# MAIN.net
KiCad netlist of a schematic drawn in Altium Designer
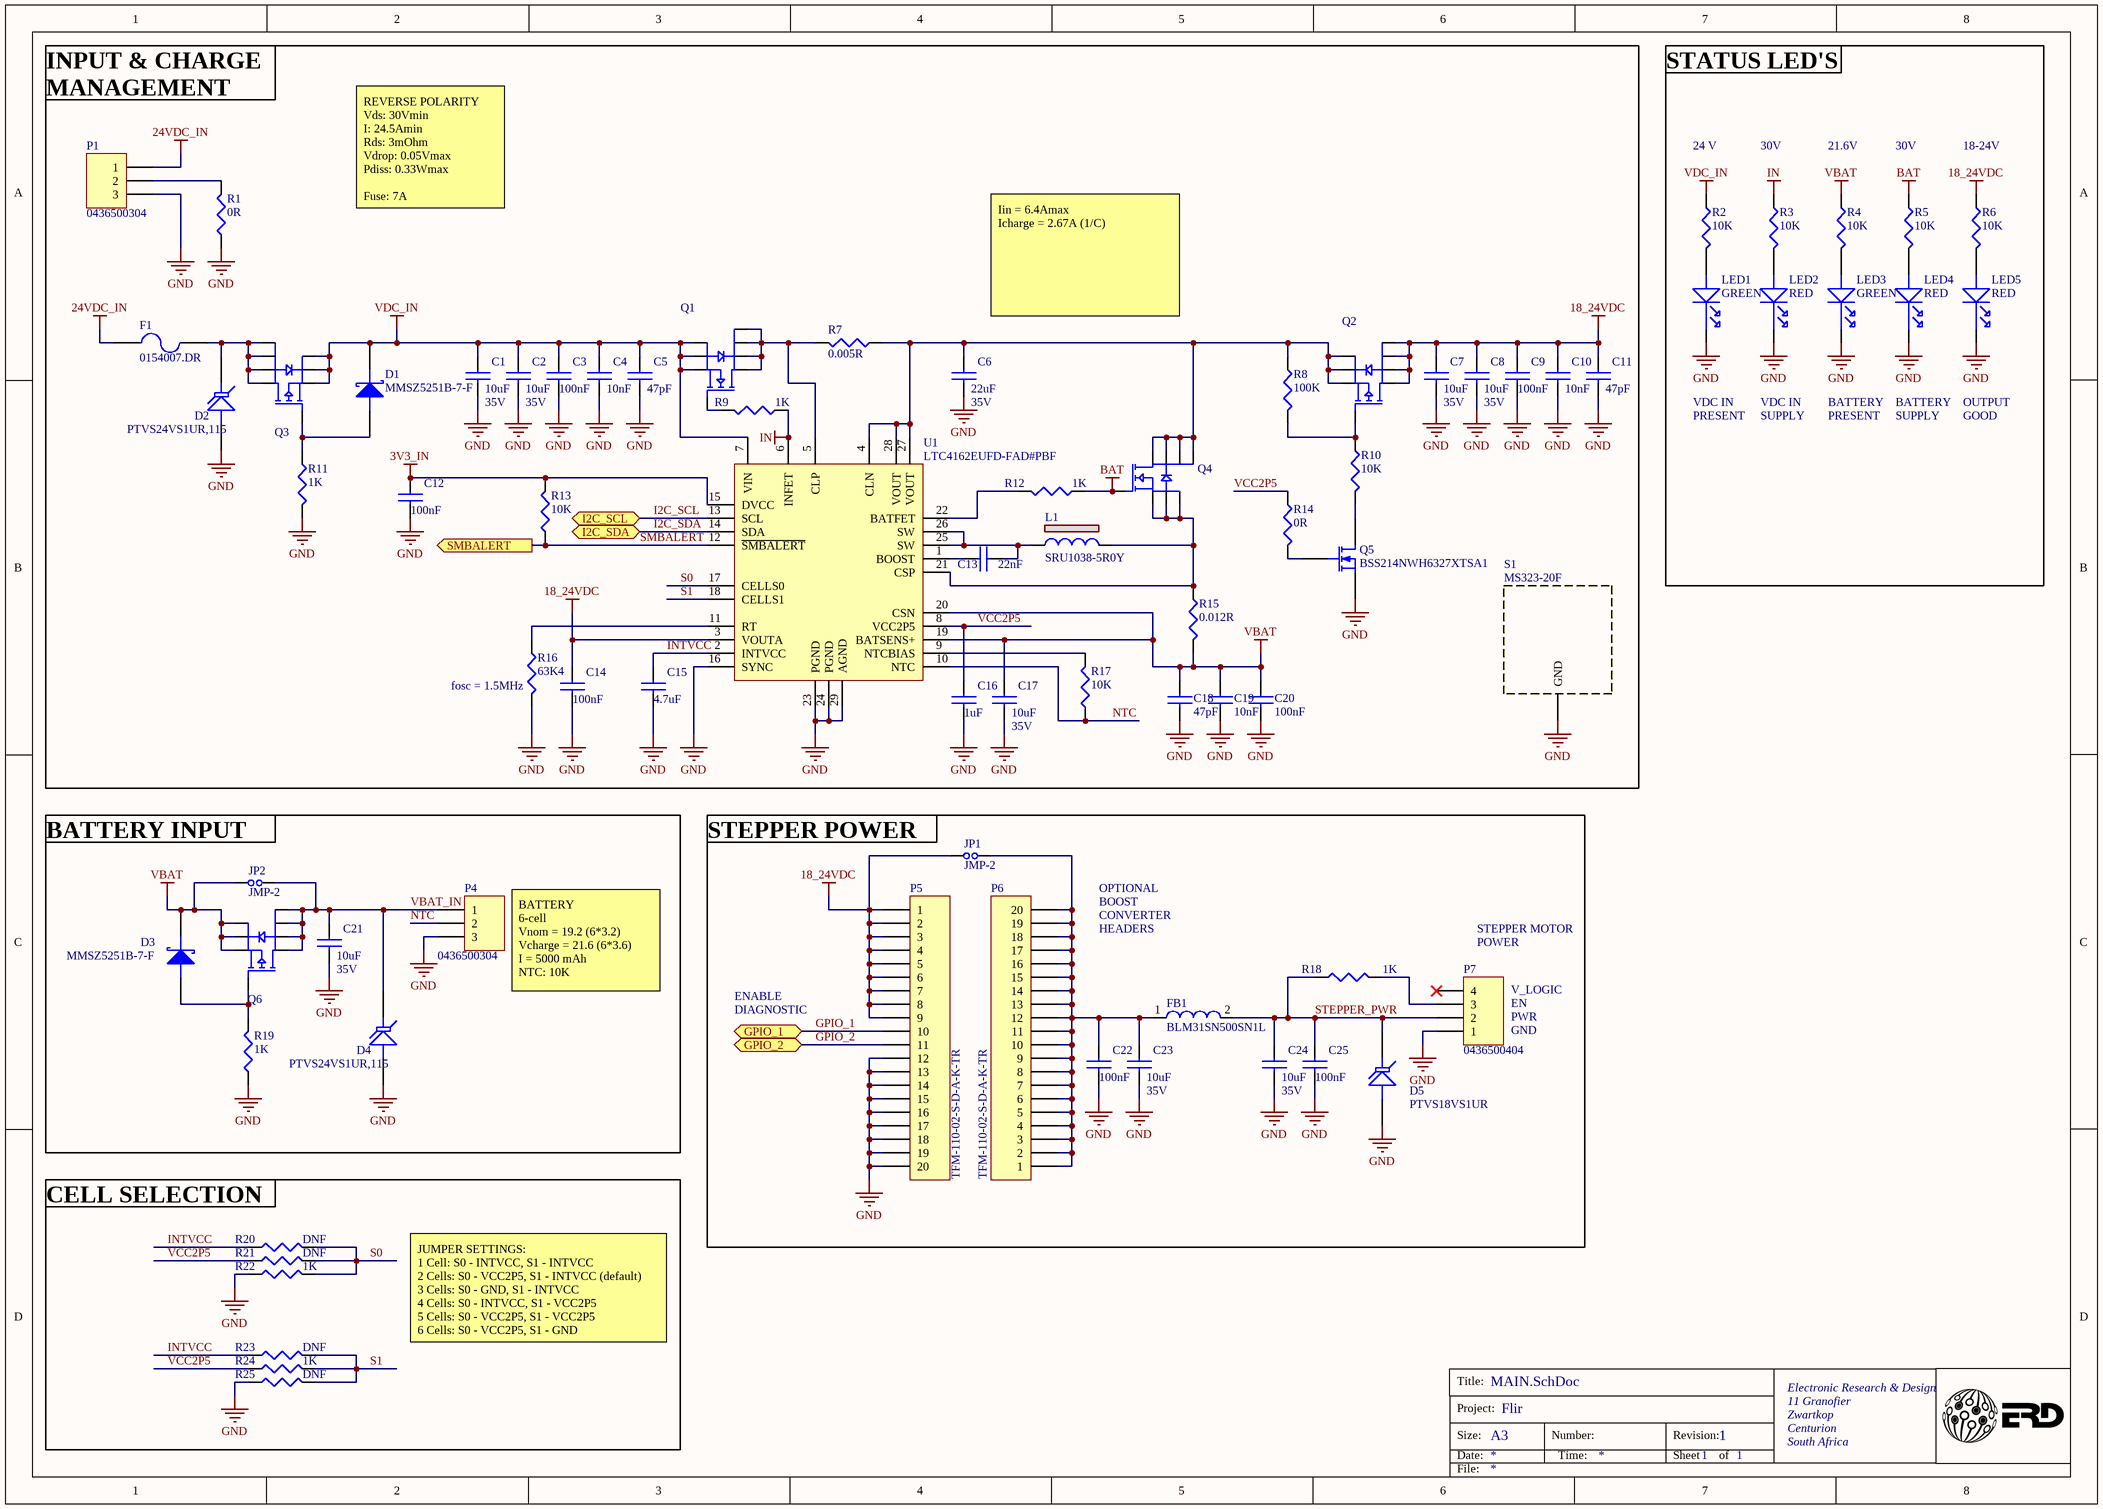
[diagram p0: MAIN.SchDoc]

(export (version "E")
  (design (tool "Eeschema 10.0.6"))
  (components
    (comp (ref "C1")
      (value "10uF")
      (footprint "CC0805")
      (description "CAP CER 10UF 35V 10% X5R 0805")
      (fields
        (field (name "MANUFACTURER") "Murata")
        (field (name "PART NUMBER") "GRM21BR6YA106KE43L")
        (field (name "VOLTAGE RATING") "35V")
      )
      (libsource (lib "ERD TiAm") (part "CAP CER 0.1UF 10V 10% X5R 0402"))
    )
    (comp (ref "C2")
      (value "10uF")
      (footprint "CC0805")
      (description "CAP CER 10UF 35V 10% X5R 0805")
      (fields
        (field (name "MANUFACTURER") "Murata")
        (field (name "PART NUMBER") "GRM21BR6YA106KE43L")
        (field (name "VOLTAGE RATING") "35V")
      )
      (libsource (lib "ERD TiAm") (part "CAP CER 0.1UF 10V 10% X5R 0402"))
    )
    (comp (ref "C3")
      (value "100nF")
      (footprint "CC0402")
      (description "CAP CER 0.1UF 50V 10% X7R 0402")
      (fields (field (name "MANUFACTURER") "Murata") (field (name "PART NUMBER") "GCM155R71H104KE02D"))
      (libsource (lib "ERD TiAm") (part "CAP CER 0.1UF 10V 10% X5R 0402"))
    )
    (comp (ref "C4")
      (value "10nF")
      (footprint "CC0402")
      (description "CAP CER 10NF 50V 10% X7R 0402")
      (fields (field (name "MANUFACTURER") "Murata") (field (name "PART NUMBER") "GRM155R71H103KA88J"))
      (libsource (lib "ERD TiAm") (part "CAP CER 0.1UF 10V 10% X5R 0402"))
    )
    (comp (ref "C5")
      (value "47pF")
      (footprint "CC0402")
      (description "CAP CER 47PF 50V 5% C0G/NP0 0402")
      (fields (field (name "MANUFACTURER") "Murata") (field (name "PART NUMBER") "GCM1555C1H470JA16D"))
      (libsource (lib "ERD TiAm") (part "CAP CER 0.1UF 10V 10% X5R 0402"))
    )
    (comp (ref "C6")
      (value "22uF")
      (footprint "RC1206")
      (description "CAP CER 22UF 35V 20% X5R 1206")
      (fields
        (field (name "MANUFACTURER") "Murata")
        (field (name "PART NUMBER") "C3216X5R1V226M160AC")
        (field (name "VOLTAGE RATING") "35V")
      )
      (libsource (lib "ERD TiAm") (part "CAP CER 0.1UF 10V 10% X5R 0402"))
    )
    (comp (ref "C7")
      (value "10uF")
      (footprint "CC0805")
      (description "CAP CER 10UF 35V 10% X5R 0805")
      (fields
        (field (name "MANUFACTURER") "Murata")
        (field (name "PART NUMBER") "GRM21BR6YA106KE43L")
        (field (name "VOLTAGE RATING") "35V")
      )
      (libsource (lib "ERD TiAm") (part "CAP CER 0.1UF 10V 10% X5R 0402"))
    )
    (comp (ref "C8")
      (value "10uF")
      (footprint "CC0805")
      (description "CAP CER 10UF 35V 10% X5R 0805")
      (fields
        (field (name "MANUFACTURER") "Murata")
        (field (name "PART NUMBER") "GRM21BR6YA106KE43L")
        (field (name "VOLTAGE RATING") "35V")
      )
      (libsource (lib "ERD TiAm") (part "CAP CER 0.1UF 10V 10% X5R 0402"))
    )
    (comp (ref "C9")
      (value "100nF")
      (footprint "CC0402")
      (description "CAP CER 0.1UF 50V 10% X7R 0402")
      (fields (field (name "MANUFACTURER") "Murata") (field (name "PART NUMBER") "GCM155R71H104KE02D"))
      (libsource (lib "ERD TiAm") (part "CAP CER 0.1UF 10V 10% X5R 0402"))
    )
    (comp (ref "C10")
      (value "10nF")
      (footprint "CC0402")
      (description "CAP CER 10NF 50V 10% X7R 0402")
      (fields (field (name "MANUFACTURER") "Murata") (field (name "PART NUMBER") "GRM155R71H103KA88J"))
      (libsource (lib "ERD TiAm") (part "CAP CER 0.1UF 10V 10% X5R 0402"))
    )
    (comp (ref "C11")
      (value "47pF")
      (footprint "CC0402")
      (description "CAP CER 47PF 50V 5% C0G/NP0 0402")
      (fields (field (name "MANUFACTURER") "Murata") (field (name "PART NUMBER") "GCM1555C1H470JA16D"))
      (libsource (lib "ERD TiAm") (part "CAP CER 0.1UF 10V 10% X5R 0402"))
    )
    (comp (ref "C12")
      (value "100nF")
      (footprint "CC0402")
      (description "CAP CER 0.1UF 50V 10% X7R 0402")
      (fields (field (name "MANUFACTURER") "Murata") (field (name "PART NUMBER") "GCM155R71H104KE02D"))
      (libsource (lib "ERD TiAm") (part "CAP CER 0.1UF 10V 10% X5R 0402"))
    )
    (comp (ref "C13")
      (value "22nF")
      (footprint "CC0402")
      (description "CAP CER 0.022UF 50V 10% X7R 0402")
      (fields (field (name "MANUFACTURER") "Murata") (field (name "PART NUMBER") "GCM155R71H223KA55D"))
      (libsource (lib "ERD TiAm") (part "CAP CER 0.1UF 10V 10% X5R 0402"))
    )
    (comp (ref "C14")
      (value "100nF")
      (footprint "CC0402")
      (description "CAP CER 0.1UF 50V 10% X7R 0402")
      (fields (field (name "MANUFACTURER") "Murata") (field (name "PART NUMBER") "GCM155R71H104KE02D"))
      (libsource (lib "ERD TiAm") (part "CAP CER 0.1UF 10V 10% X5R 0402"))
    )
    (comp (ref "C15")
      (value "4.7uF")
      (footprint "CC0603")
      (description "CAP CER 4.7UF 25V 10% X5R 0603")
      (fields (field (name "MANUFACTURER") "Murata") (field (name "PART NUMBER") "GRM188R61E475KE11D"))
      (libsource (lib "ERD TiAm") (part "CAP CER 0.1UF 10V 10% X5R 0402"))
    )
    (comp (ref "C16")
      (value "1uF")
      (footprint "CC0402")
      (description "CAP CER 1UF 10V 20% X5R 0402")
      (fields (field (name "MANUFACTURER") "Murata") (field (name "PART NUMBER") "GRM153R61A105ME95D"))
      (libsource (lib "ERD TiAm") (part "CAP CER 0.1UF 10V 10% X5R 0402"))
    )
    (comp (ref "C17")
      (value "10uF")
      (footprint "CC0805")
      (description "CAP CER 10UF 35V 10% X5R 0805")
      (fields
        (field (name "MANUFACTURER") "Murata")
        (field (name "PART NUMBER") "GRM21BR6YA106KE43L")
        (field (name "VOLTAGE RATING") "35V")
      )
      (libsource (lib "ERD TiAm") (part "CAP CER 0.1UF 10V 10% X5R 0402"))
    )
    (comp (ref "C18")
      (value "47pF")
      (footprint "CC0402")
      (description "CAP CER 47PF 50V 5% C0G/NP0 0402")
      (fields (field (name "MANUFACTURER") "Murata") (field (name "PART NUMBER") "GCM1555C1H470JA16D"))
      (libsource (lib "ERD TiAm") (part "CAP CER 0.1UF 10V 10% X5R 0402"))
    )
    (comp (ref "C19")
      (value "10nF")
      (footprint "CC0402")
      (description "CAP CER 10NF 50V 10% X7R 0402")
      (fields (field (name "MANUFACTURER") "Murata") (field (name "PART NUMBER") "GRM155R71H103KA88J"))
      (libsource (lib "ERD TiAm") (part "CAP CER 0.1UF 10V 10% X5R 0402"))
    )
    (comp (ref "C20")
      (value "100nF")
      (footprint "CC0402")
      (description "CAP CER 0.1UF 50V 10% X7R 0402")
      (fields (field (name "MANUFACTURER") "Murata") (field (name "PART NUMBER") "GCM155R71H104KE02D"))
      (libsource (lib "ERD TiAm") (part "CAP CER 0.1UF 10V 10% X5R 0402"))
    )
    (comp (ref "C21")
      (value "10uF")
      (footprint "CC0805")
      (description "CAP CER 10UF 35V 10% X5R 0805")
      (fields
        (field (name "MANUFACTURER") "Murata")
        (field (name "PART NUMBER") "GRM21BR6YA106KE43L")
        (field (name "VOLTAGE RATING") "35V")
      )
      (libsource (lib "ERD TiAm") (part "CAP CER 0.1UF 10V 10% X5R 0402"))
    )
    (comp (ref "C22")
      (value "100nF")
      (footprint "CC0402")
      (description "CAP CER 0.1UF 50V 10% X7R 0402")
      (fields (field (name "MANUFACTURER") "Murata") (field (name "PART NUMBER") "GCM155R71H104KE02D"))
      (libsource (lib "ERD TiAm") (part "CAP CER 0.1UF 10V 10% X5R 0402"))
    )
    (comp (ref "C23")
      (value "10uF")
      (footprint "CC0805")
      (description "CAP CER 10UF 35V 10% X5R 0805")
      (fields
        (field (name "MANUFACTURER") "Murata")
        (field (name "PART NUMBER") "GRM21BR6YA106KE43L")
        (field (name "VOLTAGE RATING") "35V")
      )
      (libsource (lib "ERD TiAm") (part "CAP CER 0.1UF 10V 10% X5R 0402"))
    )
    (comp (ref "C24")
      (value "10uF")
      (footprint "CC0805")
      (description "CAP CER 10UF 35V 10% X5R 0805")
      (fields
        (field (name "MANUFACTURER") "Murata")
        (field (name "PART NUMBER") "GRM21BR6YA106KE43L")
        (field (name "VOLTAGE RATING") "35V")
      )
      (libsource (lib "ERD TiAm") (part "CAP CER 0.1UF 10V 10% X5R 0402"))
    )
    (comp (ref "C25")
      (value "100nF")
      (footprint "CC0402")
      (description "CAP CER 0.1UF 50V 10% X7R 0402")
      (fields (field (name "MANUFACTURER") "Murata") (field (name "PART NUMBER") "GCM155R71H104KE02D"))
      (libsource (lib "ERD TiAm") (part "CAP CER 0.1UF 10V 10% X5R 0402"))
    )
    (comp (ref "D1")
      (value "MMSZ5251B-7-F")
      (footprint "SOD123W")
      (description "DIODE, ZENER, 22V, 5%, 500mW, SOD123")
      (libsource (lib "GadgetJD") (part "DIODE SCHOTTKY"))
    )
    (comp (ref "D2")
      (value "PTVS24VS1UR,115")
      (footprint "SOD123W")
      (description "DIODE, TVS, 24V, 400W, SOD123W")
      (libsource (lib "Miscellaneous Devices") (part "Tranzorb"))
    )
    (comp (ref "D3")
      (value "MMSZ5251B-7-F")
      (footprint "SOD123W")
      (description "DIODE, ZENER, 22V, 5%, 500mW, SOD123")
      (libsource (lib "GadgetJD") (part "DIODE SCHOTTKY"))
    )
    (comp (ref "D4")
      (value "PTVS24VS1UR,115")
      (footprint "SOD123W")
      (description "DIODE, TVS, 24V, 400W, SOD123W")
      (libsource (lib "Miscellaneous Devices") (part "Tranzorb"))
    )
    (comp (ref "D5")
      (value "PTVS18VS1UR")
      (footprint "SOD123W")
      (description "DIODE, TVS, 24V, 400W, SOD123W")
      (fields (field (name "PARTNUMBER") "PTVS24VS1UR,115"))
      (libsource (lib "Miscellaneous Devices") (part "Tranzorb"))
    )
    (comp (ref "F1")
      (value "0154007.DR")
      (footprint "OMNI_BLOK")
      (description "FUSE, OMNIBLOK, 125VAC/DC, 7A, Fast, SMD")
      (fields (field (name "MANUFACTURER") "Littlefuse"))
      (libsource (lib "Miscellaneous Devices") (part "Fuse 2"))
    )
    (comp (ref "FB1")
      (value "BLM31SN500SN1L")
      (footprint "RC1206")
      (description "FERRITE, 12A, 1.6mOhm, 1206")
      (libsource (lib "BEAGLEBONEBLACK_REV A5B") (part "FER_180_200_0"))
    )
    (comp (ref "JP1")
      (value "JMP-2")
      (description "Solder Jumper 2 pin")
      (libsource (lib "ERD TiAm") (part "JMP-2"))
    )
    (comp (ref "JP2")
      (value "JMP-2")
      (description "Solder Jumper 2 pin")
      (libsource (lib "ERD TiAm") (part "JMP-2"))
    )
    (comp (ref "L1")
      (value "SRU1038-5R0Y")
      (footprint "MSS1260")
      (description "IND, Power, Shielded, 5uH, 4.8A Isat, 14.5 mOHM, SMD")
      (fields (field (name "MANUFACTURER") "Bourns"))
      (libsource (lib "SCH") (part "MSS1260X"))
    )
    (comp (ref "LED1")
      (value "GREEN")
      (footprint "LED0603")
      (description "LED, GRN, 65 mcd, 0603")
      (fields (field (name "PARTNUMBER") "LTST-C194KGKT"))
      (libsource (lib "*") (part "LED"))
    )
    (comp (ref "LED2")
      (value "RED")
      (footprint "LED0603")
      (description "LED, GRN, 65 mcd, 0603")
      (fields (field (name "PARTNUMBER") "LTST-C194KRKT"))
      (libsource (lib "*") (part "LED"))
    )
    (comp (ref "LED3")
      (value "GREEN")
      (footprint "LED0603")
      (description "LED, GRN, 65 mcd, 0603")
      (fields (field (name "PARTNUMBER") "LTST-C194KGKT"))
      (libsource (lib "*") (part "LED"))
    )
    (comp (ref "LED4")
      (value "RED")
      (footprint "LED0603")
      (description "LED, GRN, 65 mcd, 0603")
      (fields (field (name "PARTNUMBER") "LTST-C194KRKT"))
      (libsource (lib "*") (part "LED"))
    )
    (comp (ref "LED5")
      (value "RED")
      (footprint "LED0603")
      (description "LED, GRN, 65 mcd, 0603")
      (fields (field (name "PARTNUMBER") "LTST-C194KRKT"))
      (libsource (lib "*") (part "LED"))
    )
    (comp (ref "P1")
      (value "0436500304")
      (footprint "HDR1X3")
      (description "Header, MicroFit, RA, 3-circuit, 3mm pitch, TH")
      (fields (field (name "MANUFACTURER") "Molex") (field (name "MATING PART") "0436450300"))
      (libsource (lib "") (part "Header 3_1"))
    )
    (comp (ref "P4")
      (value "0436500304")
      (footprint "HDR1X3")
      (description "Header, MicroFit, RA, 3-circuit, 3mm pitch, TH")
      (fields (field (name "MANUFACTURER") "Molex") (field (name "MATING PART") "0436450300"))
      (libsource (lib "Miscellaneous Connectors") (part "Header 3"))
    )
    (comp (ref "P5")
      (value "TFM-110-02-S-D-A-K-TR")
      (footprint "HDR1X20")
      (description "Header, 20 POS, 1.27mm PITCH, SMD")
      (libsource (lib "") (part "Header 20_1"))
    )
    (comp (ref "P6")
      (value "TFM-110-02-S-D-A-K-TR")
      (footprint "HDR1X20")
      (description "Header, 20 POS, 1.27mm PITCH, SMD")
      (libsource (lib "Miscellaneous Connectors") (part "Header 20"))
    )
    (comp (ref "P7")
      (value "0436500404")
      (footprint "HDR1X4")
      (description "Header, MicroFit, RA, 4-circuit, 3mm pitch, TH")
      (fields (field (name "MANUFACTURER") "Molex") (field (name "MATING PART") "0436450400"))
      (libsource (lib "Miscellaneous Connectors") (part "Header 4"))
    )
    (comp (ref "Q1")
      (value "BSC054N04NSGATMA1")
      (footprint "PG-TDSON-8 - alternate")
      (description "N-channel FET, 40V, 17A, 5.4mOhm, TDSON-8")
      (libsource (lib "SCH") (part "BSC190N15NS3"))
    )
    (comp (ref "Q2")
      (value "BSC030P03NS3GAUMA1")
      (footprint "PG-TDSON-8 - alternate")
      (description "P-channel FET, 30V, 100A, 3mOhm, TDSON-8")
      (libsource (lib "ERD TiAm") (part "p_Channel"))
    )
    (comp (ref "Q3")
      (value "BSC030P03NS3GAUMA1")
      (footprint "PG-TDSON-8 - alternate")
      (description "P-channel FET, 30V, 100A, 3mOhm, TDSON-8")
      (libsource (lib "ERD TiAm") (part "p_Channel"))
    )
    (comp (ref "Q4")
      (value "BSC054N04NSGATMA1")
      (footprint "PG-TDSON-8 - alternate")
      (description "N-channel FET, 40V, 17A, 5.4mOhm, TDSON-8")
      (libsource (lib "SCH") (part "BSC190N15NS3"))
    )
    (comp (ref "Q5")
      (value "BSS214NWH6327XTSA1")
      (footprint "ERD TiAm:SOT323")
      (description "N-Channel FET, 20V, 1.5A, 140mOhm, SOT323")
      (fields (field (name "PUBLISHER") "Altium Limited"))
      (libsource (lib "Miscellaneous Devices") (part "MOSFET-N"))
    )
    (comp (ref "Q6")
      (value "BSC030P03NS3GAUMA1")
      (footprint "PG-TDSON-8 - alternate")
      (description "P-channel FET, 30V, 100A, 3mOhm, TDSON-8")
      (libsource (lib "ERD TiAm") (part "p_Channel"))
    )
    (comp (ref "R1")
      (value "0R")
      (footprint "RC0402")
      (description "RES, 0 OHM, 1/16W, 1%, 0402")
      (fields (field (name "MANUFACTURER") "Yageo") (field (name "PARTNUMBER") "RC0402FR-070RL"))
      (libsource (lib "ERD TiAm") (part "RES_10K_1/16W_1%_0402"))
    )
    (comp (ref "R2")
      (value "10K")
      (footprint "RC0402")
      (description "RES, 10K OHM, 1/16W, 1%, 0402")
      (fields (field (name "MANUFACTURER") "Yageo") (field (name "PART NUMBER") "RC0402FR-0710KL"))
      (libsource (lib "ERD TiAm") (part "RES_10K_1/16W_1%_0402"))
    )
    (comp (ref "R3")
      (value "10K")
      (footprint "RC0402")
      (description "RES, 10K OHM, 1/16W, 1%, 0402")
      (fields (field (name "MANUFACTURER") "Yageo") (field (name "PART NUMBER") "RC0402FR-0710KL"))
      (libsource (lib "ERD TiAm") (part "RES_10K_1/16W_1%_0402"))
    )
    (comp (ref "R4")
      (value "10K")
      (footprint "RC0402")
      (description "RES, 10K OHM, 1/16W, 1%, 0402")
      (fields (field (name "MANUFACTURER") "Yageo") (field (name "PART NUMBER") "RC0402FR-0710KL"))
      (libsource (lib "ERD TiAm") (part "RES_10K_1/16W_1%_0402"))
    )
    (comp (ref "R5")
      (value "10K")
      (footprint "RC0402")
      (description "RES, 10K OHM, 1/16W, 1%, 0402")
      (fields (field (name "MANUFACTURER") "Yageo") (field (name "PART NUMBER") "RC0402FR-0710KL"))
      (libsource (lib "ERD TiAm") (part "RES_10K_1/16W_1%_0402"))
    )
    (comp (ref "R6")
      (value "10K")
      (footprint "RC0402")
      (description "RES, 10K OHM, 1/16W, 1%, 0402")
      (fields (field (name "MANUFACTURER") "Yageo") (field (name "PART NUMBER") "RC0402FR-0710KL"))
      (libsource (lib "ERD TiAm") (part "RES_10K_1/16W_1%_0402"))
    )
    (comp (ref "R7")
      (value "0.005R")
      (footprint "RC1206W")
      (description "RES, 0.005 OHM, 1W, 1%, 1206W")
      (fields
        (field (name "MANUFACTURER") "Susumu")
        (field (name "MANUFACTURER PART NUMBER") "KRL3216T4A-M-R005-F-T1")
      )
      (libsource (lib "ERD TiAm") (part "RES_0_1/16W_1%_0402"))
    )
    (comp (ref "R8")
      (value "100K")
      (footprint "RC0402")
      (description "RES, 100K OHM, 1/16W, 1%, 0402")
      (fields (field (name "MANUFACTURER") "Yageo") (field (name "PART NUMBER") "RC0402FR-07100KL"))
      (libsource (lib "ERD TiAm") (part "RES_10K_1/16W_1%_0402"))
    )
    (comp (ref "R9")
      (value "1K")
      (footprint "RC0402")
      (description "RES, 1K OHM, 1/16W, 1%, 0402")
      (fields (field (name "MANUFACTURER") "Yageo") (field (name "PARTNUMBER") "RC0402FR-071KL"))
      (libsource (lib "ERD TiAm") (part "RES_10K_1/16W_1%_0402"))
    )
    (comp (ref "R10")
      (value "10K")
      (footprint "RC0402")
      (description "RES, 10K OHM, 1/16W, 1%, 0402")
      (fields (field (name "MANUFACTURER") "Yageo") (field (name "PART NUMBER") "RC0402FR-0710KL"))
      (libsource (lib "ERD TiAm") (part "RES_10K_1/16W_1%_0402"))
    )
    (comp (ref "R11")
      (value "1K")
      (footprint "RC0402")
      (description "RES, 1K OHM, 1/16W, 1%, 0402")
      (fields (field (name "MANUFACTURER") "Yageo") (field (name "PARTNUMBER") "RC0402FR-071KL"))
      (libsource (lib "ERD TiAm") (part "RES_10K_1/16W_1%_0402"))
    )
    (comp (ref "R12")
      (value "1K")
      (footprint "RC0402")
      (description "RES, 1K OHM, 1/16W, 1%, 0402")
      (fields (field (name "MANUFACTURER") "Yageo") (field (name "PARTNUMBER") "RC0402FR-071KL"))
      (libsource (lib "ERD TiAm") (part "RES_10K_1/16W_1%_0402"))
    )
    (comp (ref "R13")
      (value "10K")
      (footprint "RC0402")
      (description "RES, 10K OHM, 1/16W, 1%, 0402")
      (fields (field (name "MANUFACTURER") "Yageo") (field (name "PART NUMBER") "RC0402FR-0710KL"))
      (libsource (lib "ERD TiAm") (part "RES_10K_1/16W_1%_0402"))
    )
    (comp (ref "R14")
      (value "0R")
      (footprint "RC0402")
      (description "RES, 0 OHM, 1/16W, 1%, 0402")
      (fields (field (name "MANUFACTURER") "Yageo") (field (name "PARTNUMBER") "RC0402FR-070RL"))
      (libsource (lib "ERD TiAm") (part "RES_10K_1/16W_1%_0402"))
    )
    (comp (ref "R15")
      (value "0.012R")
      (footprint "RC1206")
      (description "RES, 0.012 OHM, 1W, 1%, 1206")
      (fields
        (field (name "MANUFACTURER") "Panasonic")
        (field (name "MANUFACTURER PART NUMBER") "ERJ-8CWFR010V")
      )
      (libsource (lib "ERD TiAm") (part "RES_0_1/16W_1%_0402"))
    )
    (comp (ref "R16")
      (value "63K4")
      (footprint "RC0402")
      (description "RES, 63K4 OHM, 1/16W, 1%, 0402")
      (fields (field (name "MANUFACTURER") "Yageo") (field (name "PART NUMBER") "RC0402FR-0763K4L"))
      (libsource (lib "ERD TiAm") (part "RES_10K_1/16W_1%_0402"))
    )
    (comp (ref "R17")
      (value "10K")
      (footprint "RC0402")
      (description "RES, 10K OHM, 1/16W, 1%, 0402")
      (fields (field (name "MANUFACTURER") "Yageo") (field (name "PART NUMBER") "RC0402FR-0710KL"))
      (libsource (lib "ERD TiAm") (part "RES_10K_1/16W_1%_0402"))
    )
    (comp (ref "R18")
      (value "1K")
      (footprint "RC0402")
      (description "RES, 1K OHM, 1/16W, 1%, 0402")
      (fields (field (name "MANUFACTURER") "Yageo") (field (name "PARTNUMBER") "RC0402FR-071KL"))
      (libsource (lib "ERD TiAm") (part "RES_10K_1/16W_1%_0402"))
    )
    (comp (ref "R19")
      (value "1K")
      (footprint "RC0402")
      (description "RES, 1K OHM, 1/16W, 1%, 0402")
      (fields (field (name "MANUFACTURER") "Yageo") (field (name "PARTNUMBER") "RC0402FR-071KL"))
      (libsource (lib "ERD TiAm") (part "RES_10K_1/16W_1%_0402"))
    )
    (comp (ref "R20")
      (value "DNF")
      (footprint "RC0402")
      (description "RES, 1K OHM, 1/16W, 1%, 0402")
      (fields (field (name "MANUFACTURER") "Yageo") (field (name "PART NUMBER") "RC0402FR-071KL"))
      (libsource (lib "ERD TiAm") (part "RES_10K_1/16W_1%_0402"))
    )
    (comp (ref "R21")
      (value "DNF")
      (footprint "RC0402")
      (description "RES, 1K OHM, 1/16W, 1%, 0402")
      (fields (field (name "MANUFACTURER") "Yageo") (field (name "PART NUMBER") "RC0402FR-071KL"))
      (libsource (lib "ERD TiAm") (part "RES_10K_1/16W_1%_0402"))
    )
    (comp (ref "R22")
      (value "1K")
      (footprint "RC0402")
      (description "RES, 1K OHM, 1/16W, 1%, 0402")
      (fields (field (name "MANUFACTURER") "Yageo") (field (name "PART NUMBER") "RC0402FR-071KL"))
      (libsource (lib "ERD TiAm") (part "RES_10K_1/16W_1%_0402"))
    )
    (comp (ref "R23")
      (value "DNF")
      (footprint "RC0402")
      (description "RES, 1K OHM, 1/16W, 1%, 0402")
      (fields (field (name "MANUFACTURER") "Yageo") (field (name "PART NUMBER") "RC0402FR-071KL"))
      (libsource (lib "ERD TiAm") (part "RES_10K_1/16W_1%_0402"))
    )
    (comp (ref "R24")
      (value "1K")
      (footprint "RC0402")
      (description "RES, 1K OHM, 1/16W, 1%, 0402")
      (fields (field (name "MANUFACTURER") "Yageo") (field (name "PART NUMBER") "RC0402FR-071KL"))
      (libsource (lib "ERD TiAm") (part "RES_10K_1/16W_1%_0402"))
    )
    (comp (ref "R25")
      (value "DNF")
      (footprint "RC0402")
      (description "RES, 1K OHM, 1/16W, 1%, 0402")
      (fields (field (name "MANUFACTURER") "Yageo") (field (name "PART NUMBER") "RC0402FR-071KL"))
      (libsource (lib "ERD TiAm") (part "RES_10K_1/16W_1%_0402"))
    )
    (comp (ref "S1")
      (value "MS323-20F")
      (footprint "2118727-2")
      (description "RF Shield, 32.9mm x 24.4mm x 4.7mm")
      (fields (field (name "MATING PART") "MS323-20C"))
      (libsource (lib "ERD TiAm") (part "BMI-S-206-F"))
    )
    (comp (ref "U1")
      (value "LTC4162EUFD-FAD#PBF")
      (footprint "QFN-28 LTC")
      (description "Multi-Cell LiFePO4 Charger, 35V, 3.2A, QFN-28")
      (libsource (lib "ERD TiAm") (part "LTC4162"))
    )
  )
  (nets
    (net (code "1") (name "/GPIO_1") (class "Default")
      (node (ref "P5") (pin "10") (pinfunction "10_10") (pintype "passive"))
    )
    (net (code "2") (name "/GPIO_2") (class "Default")
      (node (ref "P5") (pin "11") (pinfunction "11_11") (pintype "passive"))
    )
    (net (code "3") (name "/I2C_SCL") (class "Default")
      (node (ref "U1") (pin "13") (pinfunction "SCL_13") (pintype "passive"))
    )
    (net (code "4") (name "/I2C_SDA") (class "Default")
      (node (ref "U1") (pin "14") (pinfunction "SDA_14") (pintype "passive"))
    )
    (net (code "5") (name "/INTVCC") (class "Default")
      (node (ref "C15") (pin "1") (pinfunction "1_1") (pintype "passive"))
      (node (ref "R20") (pin "1") (pinfunction "1_1") (pintype "passive"))
      (node (ref "R23") (pin "1") (pinfunction "1_1") (pintype "passive"))
      (node (ref "U1") (pin "2") (pinfunction "INTVCC_2") (pintype "passive"))
    )
    (net (code "6") (name "/NTC") (class "Default")
      (node (ref "P4") (pin "2") (pinfunction "2_2") (pintype "passive"))
      (node (ref "R17") (pin "1") (pinfunction "1_1") (pintype "passive"))
      (node (ref "U1") (pin "10") (pinfunction "NTC_10") (pintype "passive"))
    )
    (net (code "7") (name "/S0") (class "Default")
      (node (ref "R20") (pin "2") (pinfunction "2_2") (pintype "passive"))
      (node (ref "R21") (pin "2") (pinfunction "2_2") (pintype "passive"))
      (node (ref "R22") (pin "2") (pinfunction "2_2") (pintype "passive"))
      (node (ref "U1") (pin "17") (pinfunction "CELLS0_17") (pintype "passive"))
    )
    (net (code "8") (name "/S1") (class "Default")
      (node (ref "R23") (pin "2") (pinfunction "2_2") (pintype "passive"))
      (node (ref "R24") (pin "2") (pinfunction "2_2") (pintype "passive"))
      (node (ref "R25") (pin "2") (pinfunction "2_2") (pintype "passive"))
      (node (ref "U1") (pin "18") (pinfunction "CELLS1_18") (pintype "passive"))
    )
    (net (code "9") (name "/SMBALERT") (class "Default")
      (node (ref "R13") (pin "1") (pinfunction "1_1") (pintype "passive"))
      (node (ref "U1") (pin "12") (pinfunction "~{SMBALERT}_12") (pintype "passive"))
    )
    (net (code "10") (name "/STEPPER_PWR") (class "Default")
      (node (ref "C24") (pin "1") (pinfunction "1_1") (pintype "passive"))
      (node (ref "C25") (pin "1") (pinfunction "1_1") (pintype "passive"))
      (node (ref "D5") (pin "1") (pinfunction "1_1") (pintype "passive"))
      (node (ref "FB1") (pin "2") (pinfunction "2_2") (pintype "passive"))
      (node (ref "P7") (pin "2") (pinfunction "2_2") (pintype "passive"))
      (node (ref "R18") (pin "1") (pinfunction "1_1") (pintype "passive"))
    )
    (net (code "11") (name "/VBAT_IN") (class "Default")
      (node (ref "C21") (pin "1") (pinfunction "1_1") (pintype "passive"))
      (node (ref "D4") (pin "1") (pinfunction "1_1") (pintype "passive"))
      (node (ref "JP2") (pin "2") (pinfunction "2_2") (pintype "passive"))
      (node (ref "P4") (pin "1") (pinfunction "1_1") (pintype "passive"))
      (node (ref "Q6") (pin "5") (pinfunction "DRAIN_5") (pintype "passive"))
      (node (ref "Q6") (pin "6") (pinfunction "DRAIN_6") (pintype "passive"))
      (node (ref "Q6") (pin "7") (pinfunction "DRAIN_7") (pintype "passive"))
      (node (ref "Q6") (pin "8") (pinfunction "DRAIN_8") (pintype "passive"))
    )
    (net (code "12") (name "/VCC2P5") (class "Default")
      (node (ref "C16") (pin "1") (pinfunction "1_1") (pintype "passive"))
      (node (ref "R14") (pin "1") (pinfunction "1_1") (pintype "passive"))
      (node (ref "R21") (pin "1") (pinfunction "1_1") (pintype "passive"))
      (node (ref "R24") (pin "1") (pinfunction "1_1") (pintype "passive"))
      (node (ref "U1") (pin "8") (pinfunction "VCC2P5_8") (pintype "passive"))
    )
    (net (code "13") (name "3V3_IN") (class "Default")
      (node (ref "C12") (pin "1") (pinfunction "1_1") (pintype "passive"))
      (node (ref "R13") (pin "2") (pinfunction "2_2") (pintype "passive"))
      (node (ref "U1") (pin "15") (pinfunction "DVCC_15") (pintype "passive"))
    )
    (net (code "14") (name "18_24VDC") (class "Default")
      (node (ref "C10") (pin "1") (pinfunction "1_1") (pintype "passive"))
      (node (ref "C11") (pin "1") (pinfunction "1_1") (pintype "passive"))
      (node (ref "C14") (pin "1") (pinfunction "1_1") (pintype "passive"))
      (node (ref "C7") (pin "1") (pinfunction "1_1") (pintype "passive"))
      (node (ref "C8") (pin "1") (pinfunction "1_1") (pintype "passive"))
      (node (ref "C9") (pin "1") (pinfunction "1_1") (pintype "passive"))
      (node (ref "JP1") (pin "1") (pinfunction "1_1") (pintype "passive"))
      (node (ref "P5") (pin "1") (pinfunction "1_1") (pintype "passive"))
      (node (ref "P5") (pin "2") (pinfunction "2_2") (pintype "passive"))
      (node (ref "P5") (pin "3") (pinfunction "3_3") (pintype "passive"))
      (node (ref "P5") (pin "4") (pinfunction "4_4") (pintype "passive"))
      (node (ref "P5") (pin "5") (pinfunction "5_5") (pintype "passive"))
      (node (ref "P5") (pin "6") (pinfunction "6_6") (pintype "passive"))
      (node (ref "P5") (pin "7") (pinfunction "7_7") (pintype "passive"))
      (node (ref "P5") (pin "8") (pinfunction "8_8") (pintype "passive"))
      (node (ref "P5") (pin "9") (pinfunction "9_9") (pintype "passive"))
      (node (ref "Q2") (pin "5") (pinfunction "DRAIN_5") (pintype "passive"))
      (node (ref "Q2") (pin "6") (pinfunction "DRAIN_6") (pintype "passive"))
      (node (ref "Q2") (pin "7") (pinfunction "DRAIN_7") (pintype "passive"))
      (node (ref "Q2") (pin "8") (pinfunction "DRAIN_8") (pintype "passive"))
      (node (ref "R6") (pin "1") (pinfunction "1_1") (pintype "passive"))
      (node (ref "U1") (pin "3") (pinfunction "VOUTA_3") (pintype "passive"))
    )
    (net (code "15") (name "24VDC_IN") (class "Default")
      (node (ref "F1") (pin "1") (pinfunction "1_1") (pintype "passive"))
      (node (ref "P1") (pin "1") (pinfunction "1_1") (pintype "passive"))
    )
    (net (code "16") (name "BAT") (class "Default")
      (node (ref "Q4") (pin "4") (pinfunction "G_4") (pintype "passive"))
      (node (ref "R12") (pin "2") (pinfunction "2_2") (pintype "passive"))
      (node (ref "R5") (pin "1") (pinfunction "1_1") (pintype "passive"))
    )
    (net (code "17") (name "GND") (class "Default")
      (node (ref "C1") (pin "2") (pinfunction "2_2") (pintype "passive"))
      (node (ref "C10") (pin "2") (pinfunction "2_2") (pintype "passive"))
      (node (ref "C11") (pin "2") (pinfunction "2_2") (pintype "passive"))
      (node (ref "C12") (pin "2") (pinfunction "2_2") (pintype "passive"))
      (node (ref "C14") (pin "2") (pinfunction "2_2") (pintype "passive"))
      (node (ref "C15") (pin "2") (pinfunction "2_2") (pintype "passive"))
      (node (ref "C16") (pin "2") (pinfunction "2_2") (pintype "passive"))
      (node (ref "C17") (pin "2") (pinfunction "2_2") (pintype "passive"))
      (node (ref "C18") (pin "2") (pinfunction "2_2") (pintype "passive"))
      (node (ref "C19") (pin "2") (pinfunction "2_2") (pintype "passive"))
      (node (ref "C2") (pin "2") (pinfunction "2_2") (pintype "passive"))
      (node (ref "C20") (pin "2") (pinfunction "2_2") (pintype "passive"))
      (node (ref "C21") (pin "2") (pinfunction "2_2") (pintype "passive"))
      (node (ref "C22") (pin "2") (pinfunction "2_2") (pintype "passive"))
      (node (ref "C23") (pin "2") (pinfunction "2_2") (pintype "passive"))
      (node (ref "C24") (pin "2") (pinfunction "2_2") (pintype "passive"))
      (node (ref "C25") (pin "2") (pinfunction "2_2") (pintype "passive"))
      (node (ref "C3") (pin "2") (pinfunction "2_2") (pintype "passive"))
      (node (ref "C4") (pin "2") (pinfunction "2_2") (pintype "passive"))
      (node (ref "C5") (pin "2") (pinfunction "2_2") (pintype "passive"))
      (node (ref "C6") (pin "2") (pinfunction "2_2") (pintype "passive"))
      (node (ref "C7") (pin "2") (pinfunction "2_2") (pintype "passive"))
      (node (ref "C8") (pin "2") (pinfunction "2_2") (pintype "passive"))
      (node (ref "C9") (pin "2") (pinfunction "2_2") (pintype "passive"))
      (node (ref "D2") (pin "2") (pinfunction "2_2") (pintype "passive"))
      (node (ref "D4") (pin "2") (pinfunction "2_2") (pintype "passive"))
      (node (ref "D5") (pin "2") (pinfunction "2_2") (pintype "passive"))
      (node (ref "LED1") (pin "C") (pinfunction "C_C") (pintype "passive"))
      (node (ref "LED2") (pin "C") (pinfunction "C_C") (pintype "passive"))
      (node (ref "LED3") (pin "C") (pinfunction "C_C") (pintype "passive"))
      (node (ref "LED4") (pin "C") (pinfunction "C_C") (pintype "passive"))
      (node (ref "LED5") (pin "C") (pinfunction "C_C") (pintype "passive"))
      (node (ref "P1") (pin "3") (pinfunction "3_3") (pintype "passive"))
      (node (ref "P4") (pin "3") (pinfunction "3_3") (pintype "passive"))
      (node (ref "P5") (pin "12") (pinfunction "12_12") (pintype "passive"))
      (node (ref "P5") (pin "13") (pinfunction "13_13") (pintype "passive"))
      (node (ref "P5") (pin "14") (pinfunction "14_14") (pintype "passive"))
      (node (ref "P5") (pin "15") (pinfunction "15_15") (pintype "passive"))
      (node (ref "P5") (pin "16") (pinfunction "16_16") (pintype "passive"))
      (node (ref "P5") (pin "17") (pinfunction "17_17") (pintype "passive"))
      (node (ref "P5") (pin "18") (pinfunction "18_18") (pintype "passive"))
      (node (ref "P5") (pin "19") (pinfunction "19_19") (pintype "passive"))
      (node (ref "P5") (pin "20") (pinfunction "20_20") (pintype "passive"))
      (node (ref "P7") (pin "1") (pinfunction "1_1") (pintype "passive"))
      (node (ref "Q5") (pin "3") (pinfunction "S_3") (pintype "passive"))
      (node (ref "R1") (pin "1") (pinfunction "1_1") (pintype "passive"))
      (node (ref "R11") (pin "2") (pinfunction "2_2") (pintype "passive"))
      (node (ref "R16") (pin "2") (pinfunction "2_2") (pintype "passive"))
      (node (ref "R19") (pin "2") (pinfunction "2_2") (pintype "passive"))
      (node (ref "R22") (pin "1") (pinfunction "1_1") (pintype "passive"))
      (node (ref "R25") (pin "1") (pinfunction "1_1") (pintype "passive"))
      (node (ref "S1") (pin "1") (pinfunction "GND_1") (pintype "passive"))
      (node (ref "U1") (pin "16") (pinfunction "SYNC_16") (pintype "passive"))
      (node (ref "U1") (pin "23") (pinfunction "PGND_23") (pintype "passive"))
      (node (ref "U1") (pin "24") (pinfunction "PGND_24") (pintype "passive"))
      (node (ref "U1") (pin "29") (pinfunction "AGND_29") (pintype "passive"))
    )
    (net (code "18") (name "IN") (class "Default")
      (node (ref "R3") (pin "1") (pinfunction "1_1") (pintype "passive"))
      (node (ref "R9") (pin "2") (pinfunction "2_2") (pintype "passive"))
      (node (ref "U1") (pin "6") (pinfunction "INFET_6") (pintype "passive"))
    )
    (net (code "19") (name "Net-(C13-Pad2)") (class "Default")
      (node (ref "C13") (pin "2") (pinfunction "2_2") (pintype "passive"))
      (node (ref "L1") (pin "1") (pinfunction "1_1") (pintype "passive"))
      (node (ref "U1") (pin "25") (pinfunction "SW_25") (pintype "passive"))
      (node (ref "U1") (pin "26") (pinfunction "SW_26") (pintype "passive"))
    )
    (net (code "20") (name "Net-(C22-Pad1)") (class "Default")
      (node (ref "C22") (pin "1") (pinfunction "1_1") (pintype "passive"))
      (node (ref "C23") (pin "1") (pinfunction "1_1") (pintype "passive"))
      (node (ref "FB1") (pin "1") (pinfunction "1_1") (pintype "passive"))
      (node (ref "JP1") (pin "2") (pinfunction "2_2") (pintype "passive"))
      (node (ref "P6") (pin "1") (pinfunction "1_1") (pintype "passive"))
      (node (ref "P6") (pin "10") (pinfunction "10_10") (pintype "passive"))
      (node (ref "P6") (pin "11") (pinfunction "11_11") (pintype "passive"))
      (node (ref "P6") (pin "12") (pinfunction "12_12") (pintype "passive"))
      (node (ref "P6") (pin "13") (pinfunction "13_13") (pintype "passive"))
      (node (ref "P6") (pin "14") (pinfunction "14_14") (pintype "passive"))
      (node (ref "P6") (pin "15") (pinfunction "15_15") (pintype "passive"))
      (node (ref "P6") (pin "16") (pinfunction "16_16") (pintype "passive"))
      (node (ref "P6") (pin "17") (pinfunction "17_17") (pintype "passive"))
      (node (ref "P6") (pin "18") (pinfunction "18_18") (pintype "passive"))
      (node (ref "P6") (pin "19") (pinfunction "19_19") (pintype "passive"))
      (node (ref "P6") (pin "2") (pinfunction "2_2") (pintype "passive"))
      (node (ref "P6") (pin "20") (pinfunction "20_20") (pintype "passive"))
      (node (ref "P6") (pin "3") (pinfunction "3_3") (pintype "passive"))
      (node (ref "P6") (pin "4") (pinfunction "4_4") (pintype "passive"))
      (node (ref "P6") (pin "5") (pinfunction "5_5") (pintype "passive"))
      (node (ref "P6") (pin "6") (pinfunction "6_6") (pintype "passive"))
      (node (ref "P6") (pin "7") (pinfunction "7_7") (pintype "passive"))
      (node (ref "P6") (pin "8") (pinfunction "8_8") (pintype "passive"))
      (node (ref "P6") (pin "9") (pinfunction "9_9") (pintype "passive"))
    )
    (net (code "21") (name "Net-(D2-Pad1)") (class "Default")
      (node (ref "D2") (pin "1") (pinfunction "1_1") (pintype "passive"))
      (node (ref "F1") (pin "2") (pinfunction "2_2") (pintype "passive"))
      (node (ref "Q3") (pin "5") (pinfunction "DRAIN_5") (pintype "passive"))
      (node (ref "Q3") (pin "6") (pinfunction "DRAIN_6") (pintype "passive"))
      (node (ref "Q3") (pin "7") (pinfunction "DRAIN_7") (pintype "passive"))
      (node (ref "Q3") (pin "8") (pinfunction "DRAIN_8") (pintype "passive"))
    )
    (net (code "22") (name "Net-(LED1-PadA)") (class "Default")
      (node (ref "LED1") (pin "A") (pinfunction "A_A") (pintype "passive"))
      (node (ref "R2") (pin "2") (pinfunction "2_2") (pintype "passive"))
    )
    (net (code "23") (name "Net-(LED2-PadA)") (class "Default")
      (node (ref "LED2") (pin "A") (pinfunction "A_A") (pintype "passive"))
      (node (ref "R3") (pin "2") (pinfunction "2_2") (pintype "passive"))
    )
    (net (code "24") (name "Net-(LED3-PadA)") (class "Default")
      (node (ref "LED3") (pin "A") (pinfunction "A_A") (pintype "passive"))
      (node (ref "R4") (pin "2") (pinfunction "2_2") (pintype "passive"))
    )
    (net (code "25") (name "Net-(LED4-PadA)") (class "Default")
      (node (ref "LED4") (pin "A") (pinfunction "A_A") (pintype "passive"))
      (node (ref "R5") (pin "2") (pinfunction "2_2") (pintype "passive"))
    )
    (net (code "26") (name "Net-(LED5-PadA)") (class "Default")
      (node (ref "LED5") (pin "A") (pinfunction "A_A") (pintype "passive"))
      (node (ref "R6") (pin "2") (pinfunction "2_2") (pintype "passive"))
    )
    (net (code "27") (name "Net-(P1-Pad2)") (class "Default")
      (node (ref "P1") (pin "2") (pinfunction "2_2") (pintype "passive"))
      (node (ref "R1") (pin "2") (pinfunction "2_2") (pintype "passive"))
    )
    (net (code "28") (name "Net-(P7-Pad3)") (class "Default")
      (node (ref "P7") (pin "3") (pinfunction "3_3") (pintype "passive"))
      (node (ref "R18") (pin "2") (pinfunction "2_2") (pintype "passive"))
    )
    (net (code "29") (name "Net-(Q1-G)") (class "Default")
      (node (ref "Q1") (pin "4") (pinfunction "G_4") (pintype "passive"))
      (node (ref "R9") (pin "1") (pinfunction "1_1") (pintype "passive"))
    )
    (net (code "30") (name "Net-(Q2-GATE)") (class "Default")
      (node (ref "Q2") (pin "4") (pinfunction "GATE_4") (pintype "passive"))
      (node (ref "R10") (pin "1") (pinfunction "1_1") (pintype "passive"))
      (node (ref "R8") (pin "2") (pinfunction "2_2") (pintype "passive"))
    )
    (net (code "31") (name "Net-(Q3-GATE)") (class "Default")
      (node (ref "D1") (pin "2") (pinfunction "2_2") (pintype "passive"))
      (node (ref "Q3") (pin "4") (pinfunction "GATE_4") (pintype "passive"))
      (node (ref "R11") (pin "1") (pinfunction "1_1") (pintype "passive"))
    )
    (net (code "32") (name "Net-(Q5-D)") (class "Default")
      (node (ref "Q5") (pin "1") (pinfunction "D_1") (pintype "passive"))
      (node (ref "R10") (pin "2") (pinfunction "2_2") (pintype "passive"))
    )
    (net (code "33") (name "Net-(Q5-G)") (class "Default")
      (node (ref "Q5") (pin "2") (pinfunction "G_2") (pintype "passive"))
      (node (ref "R14") (pin "2") (pinfunction "2_2") (pintype "passive"))
    )
    (net (code "34") (name "Net-(Q6-GATE)") (class "Default")
      (node (ref "D3") (pin "2") (pinfunction "2_2") (pintype "passive"))
      (node (ref "Q6") (pin "4") (pinfunction "GATE_4") (pintype "passive"))
      (node (ref "R19") (pin "1") (pinfunction "1_1") (pintype "passive"))
    )
    (net (code "35") (name "Net-(U1-BATFET)") (class "Default")
      (node (ref "R12") (pin "1") (pinfunction "1_1") (pintype "passive"))
      (node (ref "U1") (pin "22") (pinfunction "BATFET_22") (pintype "passive"))
    )
    (net (code "36") (name "Net-(U1-BOOST)") (class "Default")
      (node (ref "C13") (pin "1") (pinfunction "1_1") (pintype "passive"))
      (node (ref "U1") (pin "1") (pinfunction "BOOST_1") (pintype "passive"))
    )
    (net (code "37") (name "Net-(U1-CLN)") (class "Default")
      (node (ref "C6") (pin "1") (pinfunction "1_1") (pintype "passive"))
      (node (ref "Q2") (pin "1") (pinfunction "SOURCE_1") (pintype "passive"))
      (node (ref "Q2") (pin "2") (pinfunction "SOURCE_2") (pintype "passive"))
      (node (ref "Q2") (pin "3") (pinfunction "SOURCE_3") (pintype "passive"))
      (node (ref "Q4") (pin "5") (pinfunction "D_5") (pintype "passive"))
      (node (ref "Q4") (pin "6") (pinfunction "D_6") (pintype "passive"))
      (node (ref "Q4") (pin "7") (pinfunction "D_7") (pintype "passive"))
      (node (ref "Q4") (pin "8") (pinfunction "D_8") (pintype "passive"))
      (node (ref "R7") (pin "1") (pinfunction "1_1") (pintype "passive"))
      (node (ref "R8") (pin "1") (pinfunction "1_1") (pintype "passive"))
      (node (ref "U1") (pin "27") (pinfunction "VOUT_27") (pintype "passive"))
      (node (ref "U1") (pin "28") (pinfunction "VOUT_28") (pintype "passive"))
      (node (ref "U1") (pin "4") (pinfunction "CLN_4") (pintype "passive"))
    )
    (net (code "38") (name "Net-(U1-CLP)") (class "Default")
      (node (ref "Q1") (pin "5") (pinfunction "D_5") (pintype "passive"))
      (node (ref "Q1") (pin "6") (pinfunction "D_6") (pintype "passive"))
      (node (ref "Q1") (pin "7") (pinfunction "D_7") (pintype "passive"))
      (node (ref "Q1") (pin "8") (pinfunction "D_8") (pintype "passive"))
      (node (ref "R7") (pin "2") (pinfunction "2_2") (pintype "passive"))
      (node (ref "U1") (pin "5") (pinfunction "CLP_5") (pintype "passive"))
    )
    (net (code "39") (name "Net-(U1-CSP)") (class "Default")
      (node (ref "L1") (pin "2") (pinfunction "2_2") (pintype "passive"))
      (node (ref "Q4") (pin "1") (pinfunction "S_1") (pintype "passive"))
      (node (ref "Q4") (pin "2") (pinfunction "S_2") (pintype "passive"))
      (node (ref "Q4") (pin "3") (pinfunction "S_3") (pintype "passive"))
      (node (ref "R15") (pin "1") (pinfunction "1_1") (pintype "passive"))
      (node (ref "U1") (pin "21") (pinfunction "CSP_21") (pintype "passive"))
    )
    (net (code "40") (name "Net-(U1-NTCBIAS)") (class "Default")
      (node (ref "R17") (pin "2") (pinfunction "2_2") (pintype "passive"))
      (node (ref "U1") (pin "9") (pinfunction "NTCBIAS_9") (pintype "passive"))
    )
    (net (code "41") (name "Net-(U1-RT)") (class "Default")
      (node (ref "R16") (pin "1") (pinfunction "1_1") (pintype "passive"))
      (node (ref "U1") (pin "11") (pinfunction "RT_11") (pintype "passive"))
    )
    (net (code "42") (name "VBAT") (class "Default")
      (node (ref "C17") (pin "1") (pinfunction "1_1") (pintype "passive"))
      (node (ref "C18") (pin "1") (pinfunction "1_1") (pintype "passive"))
      (node (ref "C19") (pin "1") (pinfunction "1_1") (pintype "passive"))
      (node (ref "C20") (pin "1") (pinfunction "1_1") (pintype "passive"))
      (node (ref "D3") (pin "1") (pinfunction "1_1") (pintype "passive"))
      (node (ref "JP2") (pin "1") (pinfunction "1_1") (pintype "passive"))
      (node (ref "Q6") (pin "1") (pinfunction "SOURCE_1") (pintype "passive"))
      (node (ref "Q6") (pin "2") (pinfunction "SOURCE_2") (pintype "passive"))
      (node (ref "Q6") (pin "3") (pinfunction "SOURCE_3") (pintype "passive"))
      (node (ref "R15") (pin "2") (pinfunction "2_2") (pintype "passive"))
      (node (ref "R4") (pin "1") (pinfunction "1_1") (pintype "passive"))
      (node (ref "U1") (pin "19") (pinfunction "BATSENS+_19") (pintype "passive"))
      (node (ref "U1") (pin "20") (pinfunction "CSN_20") (pintype "passive"))
    )
    (net (code "43") (name "VDC_IN") (class "Default")
      (node (ref "C1") (pin "1") (pinfunction "1_1") (pintype "passive"))
      (node (ref "C2") (pin "1") (pinfunction "1_1") (pintype "passive"))
      (node (ref "C3") (pin "1") (pinfunction "1_1") (pintype "passive"))
      (node (ref "C4") (pin "1") (pinfunction "1_1") (pintype "passive"))
      (node (ref "C5") (pin "1") (pinfunction "1_1") (pintype "passive"))
      (node (ref "D1") (pin "1") (pinfunction "1_1") (pintype "passive"))
      (node (ref "Q1") (pin "1") (pinfunction "S_1") (pintype "passive"))
      (node (ref "Q1") (pin "2") (pinfunction "S_2") (pintype "passive"))
      (node (ref "Q1") (pin "3") (pinfunction "S_3") (pintype "passive"))
      (node (ref "Q3") (pin "1") (pinfunction "SOURCE_1") (pintype "passive"))
      (node (ref "Q3") (pin "2") (pinfunction "SOURCE_2") (pintype "passive"))
      (node (ref "Q3") (pin "3") (pinfunction "SOURCE_3") (pintype "passive"))
      (node (ref "R2") (pin "1") (pinfunction "1_1") (pintype "passive"))
      (node (ref "U1") (pin "7") (pinfunction "VIN_7") (pintype "passive"))
    )
    (net (code "44") (name "unconnected-(P7-Pad4)") (class "Default")
      (node (ref "P7") (pin "4") (pinfunction "4_4") (pintype "passive+no_connect"))
    )
  )
)
